# LEDmainb.net
KiCad netlist of a schematic drawn in Altium Designer
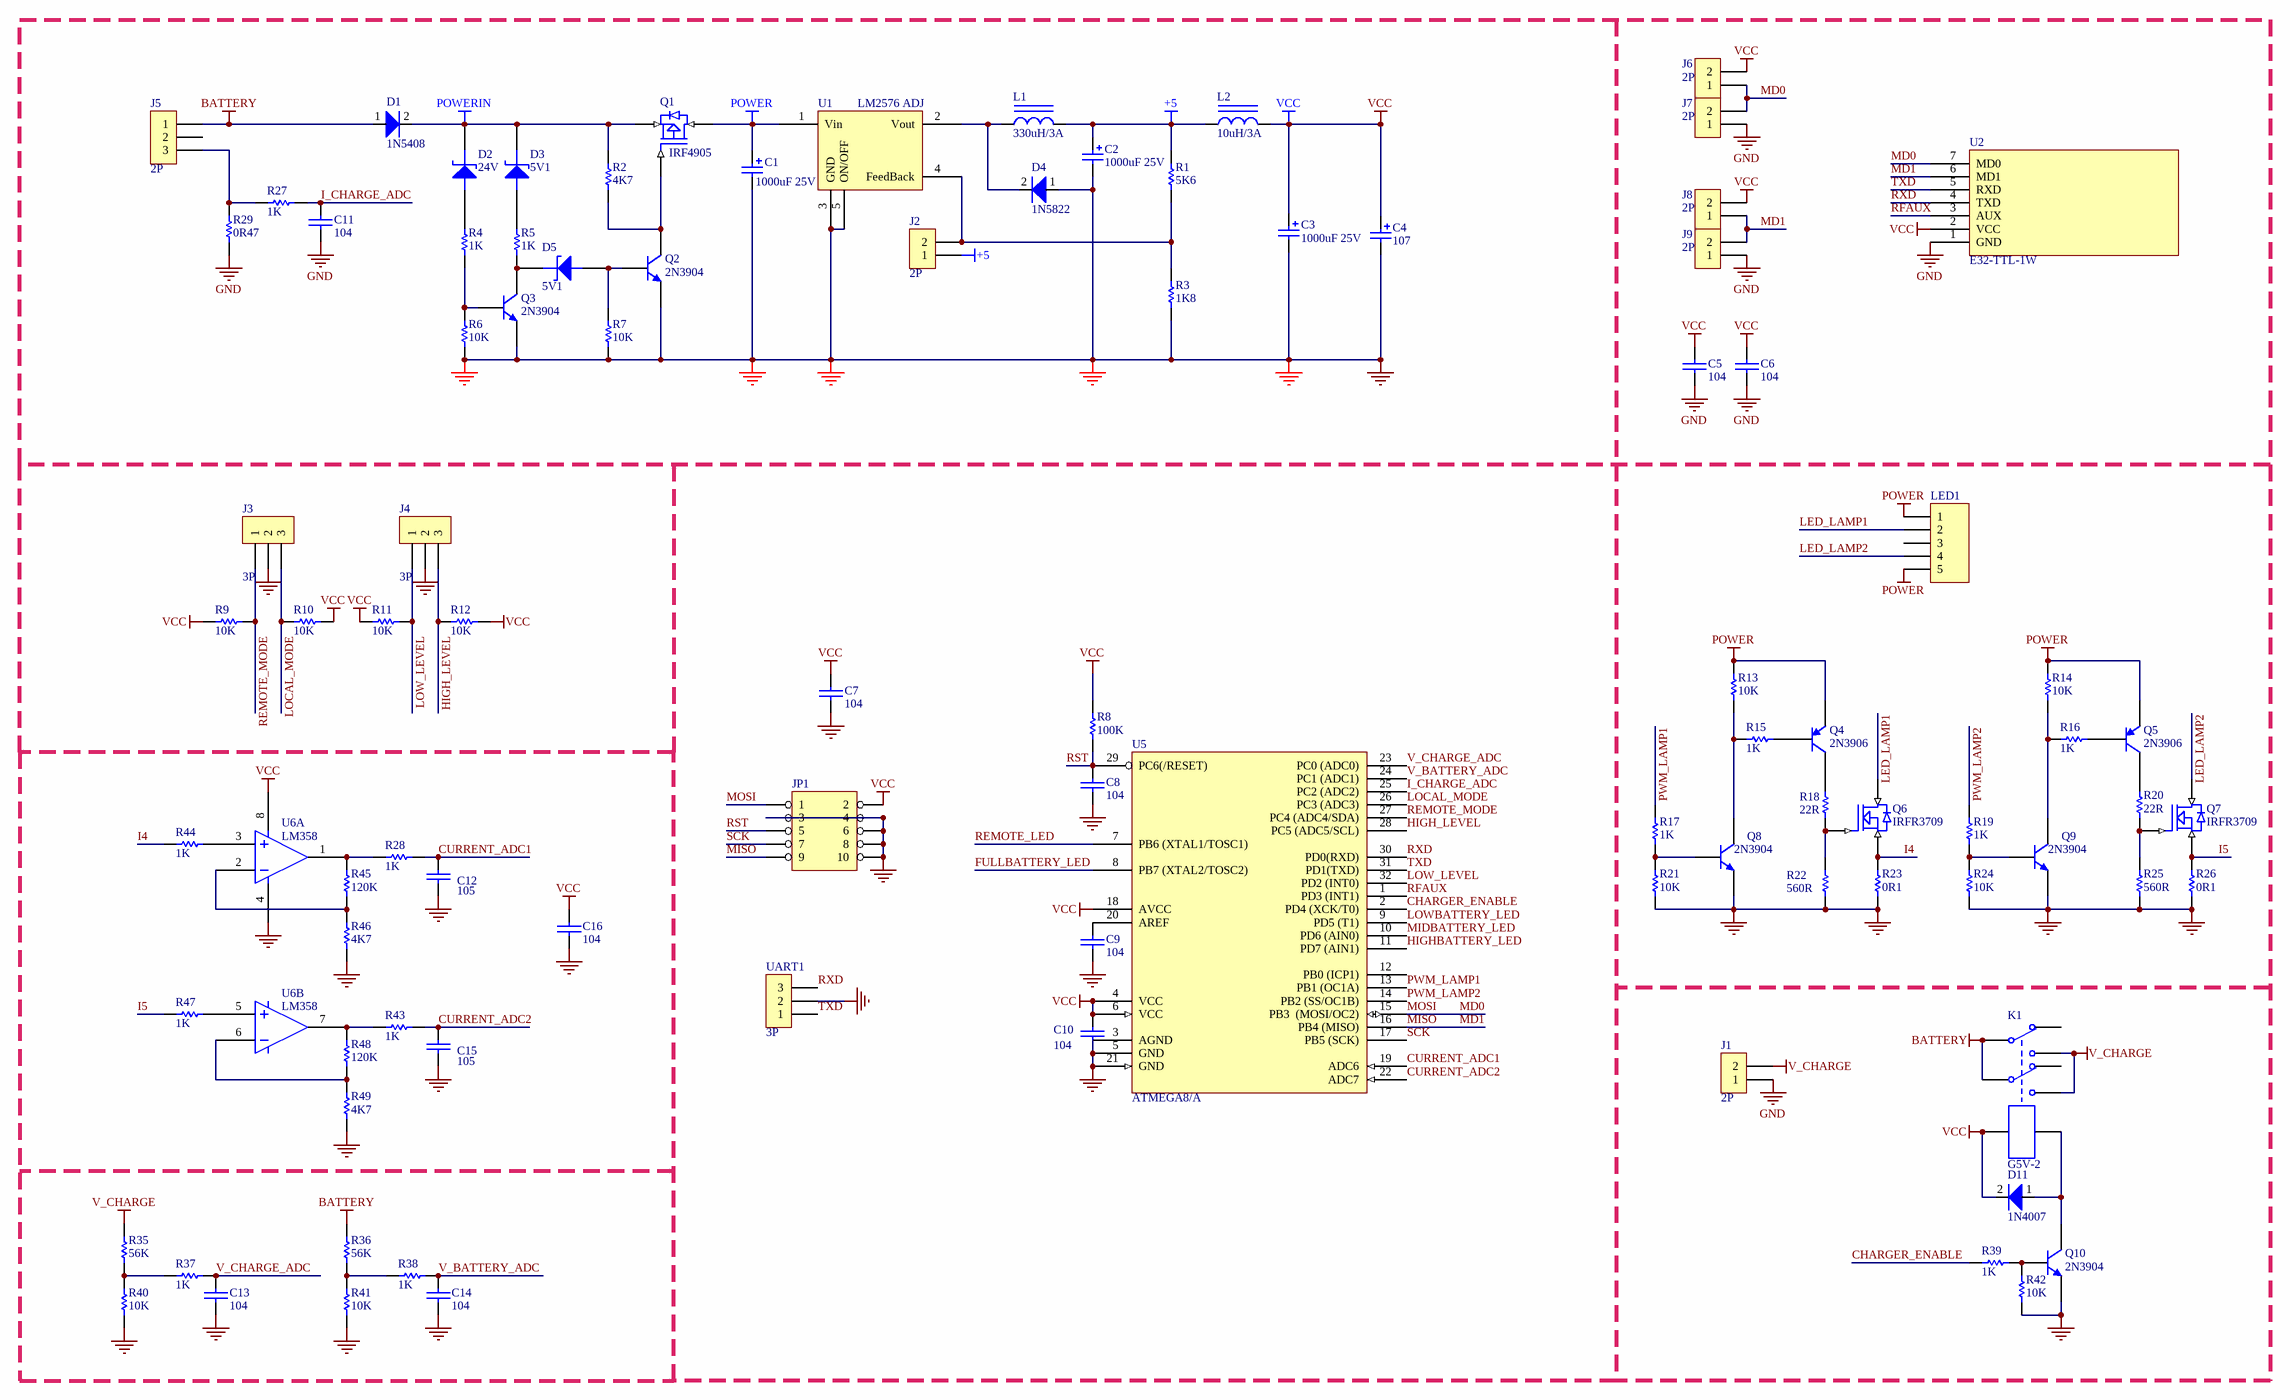
[diagram p0: LEDmainb.SchDoc]

(export (version "E")
  (design (tool "Eeschema 10.0.6"))
  (components
    (comp (ref "C1")
      (value "1000uF 25V")
      (footprint "CAP40x20L")
      (description "Polarized Capacitor (Radial)")
      (fields (field (name "Comment") "Tụ hóa chân cắm1000uF 25V") (field (name "PUBLISHER") "*"))
      (libsource (lib "DnsSchLib") (part "Cap Pol1"))
    )
    (comp (ref "C2")
      (value "1000uF 25V")
      (footprint "CAP40x20L")
      (description "Polarized Capacitor (Radial)")
      (fields (field (name "Comment") "Tụ hóa chân cắm1000uF 25V") (field (name "PUBLISHER") "*"))
      (libsource (lib "DnsSchLib") (part "Cap Pol1"))
    )
    (comp (ref "C3")
      (value "1000uF 25V")
      (footprint "CAP40x20L")
      (description "Polarized Capacitor (Radial)")
      (fields (field (name "Comment") "Tụ hóa chân cắm1000uF 25V") (field (name "PUBLISHER") "*"))
      (libsource (lib "DnsSchLib") (part "Cap Pol1"))
    )
    (comp (ref "C4")
      (value "107")
      (footprint "SMC_E/WA")
      (description "Polarized Capacitor (Radial)")
      (fields (field (name "Comment") "Tụ hóa chân dán107") (field (name "PUBLISHER") "*"))
      (libsource (lib "DnsSchLib") (part "Cap Pol1"))
    )
    (comp (ref "C5")
      (value "104")
      (footprint "0805C")
      (fields (field (name "Comment") "Tụ điện dán 0805104"))
      (libsource (lib "DnsSchLib") (part "CAP"))
    )
    (comp (ref "C6")
      (value "104")
      (footprint "0805C")
      (fields (field (name "Comment") "Tụ điện dán 0805104"))
      (libsource (lib "DnsSchLib") (part "CAP"))
    )
    (comp (ref "C7")
      (value "104")
      (footprint "0805C")
      (fields (field (name "Comment") "Tụ điện dán 0805104"))
      (libsource (lib "DnsSchLib") (part "CAP"))
    )
    (comp (ref "C8")
      (value "104")
      (footprint "0805C")
      (fields (field (name "Comment") "Tụ điện dán 0805104"))
      (libsource (lib "DnsSchLib") (part "CAP"))
    )
    (comp (ref "C9")
      (value "104")
      (footprint "0805C")
      (fields (field (name "Comment") "Tụ điện dán 0805104"))
      (libsource (lib "DnsSchLib") (part "CAP"))
    )
    (comp (ref "C10")
      (value "104")
      (footprint "0805C")
      (fields (field (name "Comment") "Tụ điện dán 0805104"))
      (libsource (lib "DnsSchLib") (part "CAP"))
    )
    (comp (ref "C11")
      (value "104")
      (footprint "0805C")
      (fields (field (name "Comment") "Tụ điện dán 0805104"))
      (libsource (lib "DnsSchLib") (part "CAP"))
    )
    (comp (ref "C12")
      (value "105")
      (footprint "0805C")
      (fields (field (name "Comment") "Tụ điện dán 0805105"))
      (libsource (lib "DnsSchLib") (part "CAP"))
    )
    (comp (ref "C13")
      (value "104")
      (footprint "0805C")
      (fields (field (name "Comment") "Tụ điện dán 0805104"))
      (libsource (lib "DnsSchLib") (part "CAP"))
    )
    (comp (ref "C14")
      (value "104")
      (footprint "0805C")
      (fields (field (name "Comment") "Tụ điện dán 0805104"))
      (libsource (lib "DnsSchLib") (part "CAP"))
    )
    (comp (ref "C15")
      (value "105")
      (footprint "0805C")
      (fields (field (name "Comment") "Tụ điện dán 0805105"))
      (libsource (lib "DnsSchLib") (part "CAP"))
    )
    (comp (ref "C16")
      (value "104")
      (footprint "0805C")
      (fields (field (name "Comment") "Tụ điện dán 0805104"))
      (libsource (lib "DnsSchLib") (part "CAP"))
    )
    (comp (ref "D1")
      (value "1N5408")
      (footprint "1N5408")
      (fields (field (name "Comment") "Diode chỉnh lưu chân cắm 3A1N5408"))
      (libsource (lib "DnsSchLib") (part "DIODE"))
    )
    (comp (ref "D2")
      (value "24V")
      (footprint "1N4148_S")
      (description "Zener Diode")
      (fields (field (name "Comment") "Diode ổn áp zener chân cắm 1W24V"))
      (libsource (lib "DnsSchLib") (part "ZENER2"))
    )
    (comp (ref "D3")
      (value "5V1")
      (footprint "1N4148_S")
      (description "Zener Diode")
      (fields (field (name "Comment") "Diode ổn áp zener chân cắm 1W5V1"))
      (libsource (lib "DnsSchLib") (part "ZENER2"))
    )
    (comp (ref "D4")
      (value "1N5822")
      (footprint "1N5822")
      (fields (field (name "Comment") "Diode xung chân cắm 3A1N5822"))
      (libsource (lib "DnsSchLib") (part "DIODE"))
    )
    (comp (ref "D5")
      (value "5V1")
      (footprint "1N4148_S")
      (description "Zener Diode")
      (fields (field (name "Comment") "Diode ổn áp zener chân cắm 1W5V1"))
      (libsource (lib "DnsSchLib") (part "ZENER2"))
    )
    (comp (ref "D11")
      (value "1N4007")
      (footprint "DIODE1A")
      (fields (field (name "Comment") "Diode chỉnh lưu chân cắm 1A1N4007"))
      (libsource (lib "DnsSchLib") (part "DIODE"))
    )
    (comp (ref "J1")
      (value "2P")
      (footprint "JACK381_2")
      (fields (field (name "Comment") "Giắc xanh loại nằm, 300V/16A - 3.81mm2P"))
      (libsource (lib "DnsSchLib") (part "CON2"))
    )
    (comp (ref "J2")
      (value "2P")
      (footprint "XPAD")
      (fields (field (name "Comment") "Jumper2P"))
      (libsource (lib "DnsSchLib") (part "CON2"))
    )
    (comp (ref "J3")
      (value "3P")
      (footprint "HDR1x3")
      (fields (field (name "Comment") "Jump đực chân thẳng, 2.54mm3P"))
      (libsource (lib "DnsSchLib") (part "CON3"))
    )
    (comp (ref "J4")
      (value "3P")
      (footprint "HDR1x3")
      (fields (field (name "Comment") "Jump đực chân thẳng, 2.54mm3P"))
      (libsource (lib "DnsSchLib") (part "CON3"))
    )
    (comp (ref "J5")
      (value "2P")
      (footprint "JACK381_3")
      (fields (field (name "Comment") "Giắc xanh loại nằm, 300V/16A - 3.81mm2P"))
      (libsource (lib "") (part "CON3_2"))
    )
    (comp (ref "J6")
      (value "2P")
      (footprint "XPAD")
      (fields (field (name "Comment") "Jumper2P"))
      (libsource (lib "DnsSchLib") (part "CON2"))
    )
    (comp (ref "J7")
      (value "2P")
      (footprint "XPAD")
      (fields (field (name "Comment") "Jumper2P"))
      (libsource (lib "DnsSchLib") (part "CON2"))
    )
    (comp (ref "J8")
      (value "2P")
      (footprint "XPAD")
      (fields (field (name "Comment") "Jumper2P"))
      (libsource (lib "DnsSchLib") (part "CON2"))
    )
    (comp (ref "J9")
      (value "2P")
      (footprint "XPAD")
      (fields (field (name "Comment") "Jumper2P"))
      (libsource (lib "DnsSchLib") (part "CON2"))
    )
    (comp (ref "JP1")
      (value "Jump đực chân thẳng, 2 hàng chân 2.54mm 10P")
      (footprint "HDR2X5")
      (libsource (lib "*") (part "HEADER 5X2"))
    )
    (comp (ref "K1")
      (value "G5V-2")
      (footprint "RELAY")
      (description "Dual-Pole Dual-Throw Relay")
      (fields (field (name "Comment") "Relay OMRON, 8 chân cắmG5V-2") (field (name "PUBLISHER") "*"))
      (libsource (lib "DnsSchLib") (part "Relay-DPDT"))
    )
    (comp (ref "L1")
      (value "330uH/3A")
      (footprint "CAMTRONDUNG")
      (fields (field (name "Comment") "Cuộn cảm chân cắm lõi trụ330uH/3A"))
      (libsource (lib "DnsSchLib") (part "INDUCTORSMALL"))
    )
    (comp (ref "L2")
      (value "10uH/3A")
      (footprint "CAMTRONDUNG")
      (fields (field (name "Comment") "Cuộn cảm chân cắm lõi trụ10uH/3A"))
      (libsource (lib "DnsSchLib") (part "INDUCTORSMALL"))
    )
    (comp (ref "LED1")
      (value "JUMP đực chân thẳng, 2.54mm 5P")
      (footprint "HDR1X5")
      (description "Header, 5-Pin")
      (fields (field (name "PUBLISHER") "Altium Limited"))
      (libsource (lib "Miscellaneous Connectors") (part "Header 5"))
    )
    (comp (ref "Q1")
      (value "IRF4905")
      (footprint "TO220SMD")
      (fields (field (name "Comment") "Transistor trường MOSFET P, chân dán TO-263IRF4905"))
      (libsource (lib "DnsSchLib") (part "MOSFET P"))
    )
    (comp (ref "Q2")
      (value "2N3904")
      (footprint "SOT23S")
      (description "NPN Bipolar Transistor")
      (fields
        (field (name "Comment") "Transistor BJT NPN, chân dán SOT-232N3904")
        (field (name "PUBLISHER") "*")
      )
      (libsource (lib "DnsSchLib") (part "NPN"))
    )
    (comp (ref "Q3")
      (value "2N3904")
      (footprint "SOT23S")
      (description "NPN Bipolar Transistor")
      (fields
        (field (name "Comment") "Transistor BJT NPN, chân dán SOT-232N3904")
        (field (name "PUBLISHER") "*")
      )
      (libsource (lib "DnsSchLib") (part "NPN"))
    )
    (comp (ref "Q4")
      (value "2N3906")
      (footprint "SOT23S")
      (description "PNP Bipolar Transistor")
      (fields
        (field (name "Comment") "Transistor BJT PNP, chân dán SOT-232N3906")
        (field (name "PUBLISHER") "*")
      )
      (libsource (lib "DnsSchLib") (part "PNP"))
    )
    (comp (ref "Q5")
      (value "2N3906")
      (footprint "SOT23S")
      (description "PNP Bipolar Transistor")
      (fields
        (field (name "Comment") "Transistor BJT PNP, chân dán SOT-232N3906")
        (field (name "PUBLISHER") "*")
      )
      (libsource (lib "DnsSchLib") (part "PNP"))
    )
    (comp (ref "Q6")
      (value "IRFR3709")
      (footprint "TO220HSMD")
      (fields (field (name "Comment") "Transistor trường MOSFET N, chân dán TO-263IRFR3709"))
      (libsource (lib "DnsSchLib") (part "MOSFET N"))
    )
    (comp (ref "Q7")
      (value "IRFR3709")
      (footprint "TO220HSMD")
      (fields (field (name "Comment") "Transistor trường MOSFET N, chân dán TO-263IRFR3709"))
      (libsource (lib "DnsSchLib") (part "MOSFET N"))
    )
    (comp (ref "Q8")
      (value "2N3904")
      (footprint "SOT23S")
      (description "NPN Bipolar Transistor")
      (fields
        (field (name "Comment") "Transistor BJT NPN, chân dán SOT-232N3904")
        (field (name "PUBLISHER") "*")
      )
      (libsource (lib "DnsSchLib") (part "NPN"))
    )
    (comp (ref "Q9")
      (value "2N3904")
      (footprint "SOT23S")
      (description "NPN Bipolar Transistor")
      (fields
        (field (name "Comment") "Transistor BJT NPN, chân dán SOT-232N3904")
        (field (name "PUBLISHER") "*")
      )
      (libsource (lib "DnsSchLib") (part "NPN"))
    )
    (comp (ref "Q10")
      (value "2N3904")
      (footprint "SOT23S")
      (description "NPN Bipolar Transistor")
      (fields
        (field (name "Comment") "Transistor BJT NPN, chân dán SOT-232N3904")
        (field (name "PUBLISHER") "*")
      )
      (libsource (lib "DnsSchLib") (part "NPN"))
    )
    (comp (ref "R1")
      (value "5K6")
      (footprint "0805DD")
      (description "Semiconductor Resistor")
      (fields (field (name "Comment") "Điện trở dán 08055K6") (field (name "PUBLISHER") "*"))
      (libsource (lib "DnsSchLib") (part "Res Semi"))
    )
    (comp (ref "R2")
      (value "4K7")
      (footprint "0805DD")
      (description "Semiconductor Resistor")
      (fields (field (name "Comment") "Điện trở dán 08054K7") (field (name "PUBLISHER") "*"))
      (libsource (lib "DnsSchLib") (part "Res Semi"))
    )
    (comp (ref "R3")
      (value "1K8")
      (footprint "0805DD")
      (description "Semiconductor Resistor")
      (fields (field (name "Comment") "Điện trở dán 08051K8") (field (name "PUBLISHER") "*"))
      (libsource (lib "DnsSchLib") (part "Res Semi"))
    )
    (comp (ref "R4")
      (value "1K")
      (footprint "0805DD")
      (description "Semiconductor Resistor")
      (fields (field (name "Comment") "Điện trở dán 08051K") (field (name "PUBLISHER") "*"))
      (libsource (lib "DnsSchLib") (part "Res Semi"))
    )
    (comp (ref "R5")
      (value "1K")
      (footprint "0805DD")
      (description "Semiconductor Resistor")
      (fields (field (name "Comment") "Điện trở dán 08051K") (field (name "PUBLISHER") "*"))
      (libsource (lib "DnsSchLib") (part "Res Semi"))
    )
    (comp (ref "R6")
      (value "10K")
      (footprint "0805DD")
      (description "Semiconductor Resistor")
      (fields (field (name "Comment") "Điện trở dán 080510K") (field (name "PUBLISHER") "*"))
      (libsource (lib "DnsSchLib") (part "Res Semi"))
    )
    (comp (ref "R7")
      (value "10K")
      (footprint "0805DD")
      (description "Semiconductor Resistor")
      (fields (field (name "Comment") "Điện trở dán 080510K") (field (name "PUBLISHER") "*"))
      (libsource (lib "DnsSchLib") (part "Res Semi"))
    )
    (comp (ref "R8")
      (value "100K")
      (footprint "0805DD")
      (description "Semiconductor Resistor")
      (fields (field (name "Comment") "Điện trở dán 0805100K") (field (name "PUBLISHER") "*"))
      (libsource (lib "DnsSchLib") (part "Res Semi"))
    )
    (comp (ref "R9")
      (value "10K")
      (footprint "0805DD")
      (description "Semiconductor Resistor")
      (fields (field (name "Comment") "Điện trở dán 080510K") (field (name "PUBLISHER") "*"))
      (libsource (lib "DnsSchLib") (part "Res Semi"))
    )
    (comp (ref "R10")
      (value "10K")
      (footprint "0805DD")
      (description "Semiconductor Resistor")
      (fields (field (name "Comment") "Điện trở dán 080510K") (field (name "PUBLISHER") "*"))
      (libsource (lib "DnsSchLib") (part "Res Semi"))
    )
    (comp (ref "R11")
      (value "10K")
      (footprint "0805DD")
      (description "Semiconductor Resistor")
      (fields (field (name "Comment") "Điện trở dán 080510K") (field (name "PUBLISHER") "*"))
      (libsource (lib "DnsSchLib") (part "Res Semi"))
    )
    (comp (ref "R12")
      (value "10K")
      (footprint "0805DD")
      (description "Semiconductor Resistor")
      (fields (field (name "Comment") "Điện trở dán 080510K") (field (name "PUBLISHER") "*"))
      (libsource (lib "DnsSchLib") (part "Res Semi"))
    )
    (comp (ref "R13")
      (value "10K")
      (footprint "0805DD")
      (description "Semiconductor Resistor")
      (fields (field (name "Comment") "Điện trở dán 080510K") (field (name "PUBLISHER") "*"))
      (libsource (lib "DnsSchLib") (part "Res Semi"))
    )
    (comp (ref "R14")
      (value "10K")
      (footprint "0805DD")
      (description "Semiconductor Resistor")
      (fields (field (name "Comment") "Điện trở dán 080510K") (field (name "PUBLISHER") "*"))
      (libsource (lib "DnsSchLib") (part "Res Semi"))
    )
    (comp (ref "R15")
      (value "1K")
      (footprint "0805DD")
      (description "Semiconductor Resistor")
      (fields (field (name "Comment") "Điện trở dán 08051K") (field (name "PUBLISHER") "*"))
      (libsource (lib "DnsSchLib") (part "Res Semi"))
    )
    (comp (ref "R16")
      (value "1K")
      (footprint "0805DD")
      (description "Semiconductor Resistor")
      (fields (field (name "Comment") "Điện trở dán 08051K") (field (name "PUBLISHER") "*"))
      (libsource (lib "DnsSchLib") (part "Res Semi"))
    )
    (comp (ref "R17")
      (value "1K")
      (footprint "0805DD")
      (description "Semiconductor Resistor")
      (fields (field (name "Comment") "Điện trở dán 08051K") (field (name "PUBLISHER") "*"))
      (libsource (lib "DnsSchLib") (part "Res Semi"))
    )
    (comp (ref "R18")
      (value "22R")
      (footprint "0805DD")
      (description "Semiconductor Resistor")
      (fields (field (name "Comment") "Điện trở dán 080522R") (field (name "PUBLISHER") "*"))
      (libsource (lib "DnsSchLib") (part "Res Semi"))
    )
    (comp (ref "R19")
      (value "1K")
      (footprint "0805DD")
      (description "Semiconductor Resistor")
      (fields (field (name "Comment") "Điện trở dán 08051K") (field (name "PUBLISHER") "*"))
      (libsource (lib "DnsSchLib") (part "Res Semi"))
    )
    (comp (ref "R20")
      (value "22R")
      (footprint "0805DD")
      (description "Semiconductor Resistor")
      (fields (field (name "Comment") "Điện trở dán 080522R") (field (name "PUBLISHER") "*"))
      (libsource (lib "DnsSchLib") (part "Res Semi"))
    )
    (comp (ref "R21")
      (value "10K")
      (footprint "0805DD")
      (description "Semiconductor Resistor")
      (fields (field (name "Comment") "Điện trở dán 080510K") (field (name "PUBLISHER") "*"))
      (libsource (lib "DnsSchLib") (part "Res Semi"))
    )
    (comp (ref "R22")
      (value "560R")
      (footprint "0805DD")
      (description "Semiconductor Resistor")
      (fields (field (name "Comment") "Điện trở dán 0805560R") (field (name "PUBLISHER") "*"))
      (libsource (lib "DnsSchLib") (part "Res Semi"))
    )
    (comp (ref "R23")
      (value "0R1")
      (footprint "AXIAL0.8S")
      (description "Semiconductor Resistor")
      (fields (field (name "Comment") "Điện trở chân cắm 2W0R1") (field (name "PUBLISHER") "*"))
      (libsource (lib "DnsSchLib") (part "Res Semi"))
    )
    (comp (ref "R24")
      (value "10K")
      (footprint "0805DD")
      (description "Semiconductor Resistor")
      (fields (field (name "Comment") "Điện trở dán 080510K") (field (name "PUBLISHER") "*"))
      (libsource (lib "DnsSchLib") (part "Res Semi"))
    )
    (comp (ref "R25")
      (value "560R")
      (footprint "0805DD")
      (description "Semiconductor Resistor")
      (fields (field (name "Comment") "Điện trở dán 0805560R") (field (name "PUBLISHER") "*"))
      (libsource (lib "DnsSchLib") (part "Res Semi"))
    )
    (comp (ref "R26")
      (value "0R1")
      (footprint "AXIAL0.8S")
      (description "Semiconductor Resistor")
      (fields (field (name "Comment") "Điện trở chân cắm 2W0R1") (field (name "PUBLISHER") "*"))
      (libsource (lib "DnsSchLib") (part "Res Semi"))
    )
    (comp (ref "R27")
      (value "1K")
      (footprint "0805DD")
      (description "Semiconductor Resistor")
      (fields (field (name "Comment") "Điện trở dán 08051K") (field (name "PUBLISHER") "*"))
      (libsource (lib "DnsSchLib") (part "Res Semi"))
    )
    (comp (ref "R28")
      (value "1K")
      (footprint "0805DD")
      (description "Semiconductor Resistor")
      (fields (field (name "Comment") "Điện trở dán 08051K") (field (name "PUBLISHER") "*"))
      (libsource (lib "DnsSchLib") (part "Res Semi"))
    )
    (comp (ref "R29")
      (value "0R47")
      (footprint "AXIAL0.8S")
      (description "Semiconductor Resistor")
      (fields (field (name "Comment") "Điện trở chân cắm 2W0R47") (field (name "PUBLISHER") "*"))
      (libsource (lib "DnsSchLib") (part "Res Semi"))
    )
    (comp (ref "R35")
      (value "56K")
      (footprint "0805DD")
      (description "Semiconductor Resistor")
      (fields (field (name "Comment") "Điện trở dán 0805 1%56K") (field (name "PUBLISHER") "*"))
      (libsource (lib "DnsSchLib") (part "Res Semi"))
    )
    (comp (ref "R36")
      (value "56K")
      (footprint "0805DD")
      (description "Semiconductor Resistor")
      (fields (field (name "Comment") "Điện trở dán 0805 1%56K") (field (name "PUBLISHER") "*"))
      (libsource (lib "DnsSchLib") (part "Res Semi"))
    )
    (comp (ref "R37")
      (value "1K")
      (footprint "0805DD")
      (description "Semiconductor Resistor")
      (fields (field (name "Comment") "Điện trở dán 08051K") (field (name "PUBLISHER") "*"))
      (libsource (lib "DnsSchLib") (part "Res Semi"))
    )
    (comp (ref "R38")
      (value "1K")
      (footprint "0805DD")
      (description "Semiconductor Resistor")
      (fields (field (name "Comment") "Điện trở dán 08051K") (field (name "PUBLISHER") "*"))
      (libsource (lib "DnsSchLib") (part "Res Semi"))
    )
    (comp (ref "R39")
      (value "1K")
      (footprint "0805DD")
      (description "Semiconductor Resistor")
      (fields (field (name "Comment") "Điện trở dán 08051K") (field (name "PUBLISHER") "*"))
      (libsource (lib "DnsSchLib") (part "Res Semi"))
    )
    (comp (ref "R40")
      (value "10K")
      (footprint "0805DD")
      (description "Semiconductor Resistor")
      (fields (field (name "Comment") "Điện trở dán 0805 1%10K") (field (name "PUBLISHER") "*"))
      (libsource (lib "DnsSchLib") (part "Res Semi"))
    )
    (comp (ref "R41")
      (value "10K")
      (footprint "0805DD")
      (description "Semiconductor Resistor")
      (fields (field (name "Comment") "Điện trở dán 0805 1%10K") (field (name "PUBLISHER") "*"))
      (libsource (lib "DnsSchLib") (part "Res Semi"))
    )
    (comp (ref "R42")
      (value "10K")
      (footprint "0805DD")
      (description "Semiconductor Resistor")
      (fields (field (name "Comment") "Điện trở dán 080510K") (field (name "PUBLISHER") "*"))
      (libsource (lib "DnsSchLib") (part "Res Semi"))
    )
    (comp (ref "R43")
      (value "1K")
      (footprint "0805DD")
      (description "Semiconductor Resistor")
      (fields (field (name "Comment") "Điện trở dán 08051K") (field (name "PUBLISHER") "*"))
      (libsource (lib "DnsSchLib") (part "Res Semi"))
    )
    (comp (ref "R44")
      (value "1K")
      (footprint "0805DD")
      (description "Semiconductor Resistor")
      (fields (field (name "Comment") "Điện trở dán 08051K") (field (name "PUBLISHER") "*"))
      (libsource (lib "DnsSchLib") (part "Res Semi"))
    )
    (comp (ref "R45")
      (value "120K")
      (footprint "0805DD")
      (description "Semiconductor Resistor")
      (fields (field (name "Comment") "Điện trở dán 0805 1%120K") (field (name "PUBLISHER") "*"))
      (libsource (lib "DnsSchLib") (part "Res Semi"))
    )
    (comp (ref "R46")
      (value "4K7")
      (footprint "0805DD")
      (description "Semiconductor Resistor")
      (fields (field (name "Comment") "Điện trở dán 0805 1%4K7") (field (name "PUBLISHER") "*"))
      (libsource (lib "DnsSchLib") (part "Res Semi"))
    )
    (comp (ref "R47")
      (value "1K")
      (footprint "0805DD")
      (description "Semiconductor Resistor")
      (fields (field (name "Comment") "Điện trở dán 08051K") (field (name "PUBLISHER") "*"))
      (libsource (lib "DnsSchLib") (part "Res Semi"))
    )
    (comp (ref "R48")
      (value "120K")
      (footprint "0805DD")
      (description "Semiconductor Resistor")
      (fields (field (name "Comment") "Điện trở dán 0805 1%120K") (field (name "PUBLISHER") "*"))
      (libsource (lib "DnsSchLib") (part "Res Semi"))
    )
    (comp (ref "R49")
      (value "4K7")
      (footprint "0805DD")
      (description "Semiconductor Resistor")
      (fields (field (name "Comment") "Điện trở dán 0805 1%4K7") (field (name "PUBLISHER") "*"))
      (libsource (lib "DnsSchLib") (part "Res Semi"))
    )
    (comp (ref "U1")
      (value "LM2576 ADJ")
      (footprint "TO220_5CSMD2")
      (fields (field (name "Comment") "IC chuyển đổi nguồn, chân dánLM2576 ADJ"))
      (libsource (lib "DnsSchLib") (part "LM2576"))
    )
    (comp (ref "U2")
      (value "E32-TTL-1W")
      (footprint "RF_AS32")
      (description "AS32-TTL-1W")
      (fields (field (name "Comment") "Module thu phát không dây RFE32-TTL-1W"))
      (libsource (lib "DnsSchLib") (part "AS32-TTL-1W"))
    )
    (comp (ref "U5")
      (value "ATMEGA8/A")
      (footprint "ATMEGA8")
      (description "TQFP package")
      (fields (field (name "Comment") "Vi điều khiển ATMEL chân dánATMEGA8/A"))
      (libsource (lib "DnsSchLib") (part "ATMEGA8-A"))
    )
    (comp (ref "U6")
      (value "IC khuếch đại thuật toán LM358 chân dán SO-8")
      (footprint "so-8")
      (fields (field (name "NAME") "LM358"))
      (libsource (lib "DnsSchLib") (part "1458"))
    )
    (comp (ref "UART1")
      (value "3P")
      (footprint "HDR1x3")
      (fields (field (name "Comment") "Jump đực chân thẳng, 2.54mm3P"))
      (libsource (lib "") (part "CON3_1"))
    )
  )
  (nets
    (net (code "1") (name "+5") (class "Default")
      (node (ref "C2") (pin "1") (pinfunction "1_1") (pintype "passive"))
      (node (ref "J2") (pin "1") (pinfunction "1_1") (pintype "passive"))
      (node (ref "L1") (pin "2") (pinfunction "2_2") (pintype "passive"))
      (node (ref "L2") (pin "1") (pinfunction "1_1") (pintype "passive"))
      (node (ref "R1") (pin "2") (pinfunction "2_2") (pintype "passive"))
    )
    (net (code "2") (name "/CHARGER_ENABLE") (class "Default")
      (node (ref "R39") (pin "2") (pinfunction "2_2") (pintype "passive"))
      (node (ref "U5") (pin "2") (pinfunction "PD4_(XCK/T0)_2") (pintype "passive"))
    )
    (net (code "3") (name "/CURRENT_ADC1") (class "Default")
      (node (ref "C12") (pin "1") (pinfunction "1_1") (pintype "passive"))
      (node (ref "R28") (pin "1") (pinfunction "1_1") (pintype "passive"))
      (node (ref "U5") (pin "19") (pinfunction "ADC6_19") (pintype "input"))
    )
    (net (code "4") (name "/CURRENT_ADC2") (class "Default")
      (node (ref "C15") (pin "1") (pinfunction "1_1") (pintype "passive"))
      (node (ref "R43") (pin "1") (pinfunction "1_1") (pintype "passive"))
      (node (ref "U5") (pin "22") (pinfunction "ADC7_22") (pintype "input"))
    )
    (net (code "5") (name "/FULLBATTERY_LED") (class "Default")
      (node (ref "U5") (pin "8") (pinfunction "PB7_(XTAL2/TOSC2)_8") (pintype "passive"))
    )
    (net (code "6") (name "/HIGHBATTERY_LED") (class "Default")
      (node (ref "U5") (pin "11") (pinfunction "PD7_(AIN1)_11") (pintype "passive"))
    )
    (net (code "7") (name "/HIGH_LEVEL") (class "Default")
      (node (ref "J4") (pin "3") (pinfunction "3_3") (pintype "passive"))
      (node (ref "R12") (pin "2") (pinfunction "2_2") (pintype "passive"))
      (node (ref "U5") (pin "28") (pinfunction "PC5_(ADC5/SCL)_28") (pintype "passive"))
    )
    (net (code "8") (name "/I4") (class "Default")
      (node (ref "Q6") (pin "3") (pinfunction "S_3") (pintype "input"))
      (node (ref "R23") (pin "2") (pinfunction "2_2") (pintype "passive"))
      (node (ref "R44") (pin "1") (pinfunction "1_1") (pintype "passive"))
    )
    (net (code "9") (name "/I5") (class "Default")
      (node (ref "Q7") (pin "3") (pinfunction "S_3") (pintype "input"))
      (node (ref "R26") (pin "2") (pinfunction "2_2") (pintype "passive"))
      (node (ref "R47") (pin "1") (pinfunction "1_1") (pintype "passive"))
    )
    (net (code "10") (name "/I_CHARGE_ADC") (class "Default")
      (node (ref "C11") (pin "1") (pinfunction "1_1") (pintype "passive"))
      (node (ref "R27") (pin "2") (pinfunction "2_2") (pintype "passive"))
      (node (ref "U5") (pin "25") (pinfunction "PC2_(ADC2)_25") (pintype "passive"))
    )
    (net (code "11") (name "/LED_LAMP1") (class "Default")
      (node (ref "LED1") (pin "2") (pinfunction "2_2") (pintype "passive"))
      (node (ref "Q6") (pin "2") (pinfunction "D_2") (pintype "input"))
    )
    (net (code "12") (name "/LED_LAMP2") (class "Default")
      (node (ref "LED1") (pin "4") (pinfunction "4_4") (pintype "passive"))
      (node (ref "Q7") (pin "2") (pinfunction "D_2") (pintype "input"))
    )
    (net (code "13") (name "/LOCAL_MODE") (class "Default")
      (node (ref "J3") (pin "3") (pinfunction "3_3") (pintype "passive"))
      (node (ref "R10") (pin "1") (pinfunction "1_1") (pintype "passive"))
      (node (ref "U5") (pin "26") (pinfunction "PC3_(ADC3)_26") (pintype "passive"))
    )
    (net (code "14") (name "/LOWBATTERY_LED") (class "Default")
      (node (ref "U5") (pin "9") (pinfunction "PD5_(T1)_9") (pintype "passive"))
    )
    (net (code "15") (name "/LOW_LEVEL") (class "Default")
      (node (ref "J4") (pin "1") (pinfunction "1_1") (pintype "passive"))
      (node (ref "R11") (pin "2") (pinfunction "2_2") (pintype "passive"))
      (node (ref "U5") (pin "32") (pinfunction "PD2_(INT0)_32") (pintype "passive"))
    )
    (net (code "16") (name "/MD0") (class "Default")
      (node (ref "J6") (pin "1") (pinfunction "1_1") (pintype "passive"))
      (node (ref "J7") (pin "2") (pinfunction "2_2") (pintype "passive"))
      (node (ref "JP1") (pin "1") (pinfunction "1_1") (pintype "passive"))
      (node (ref "U2") (pin "7") (pinfunction "MD0_7") (pintype "passive"))
      (node (ref "U5") (pin "15") (pinfunction "PB3__(MOSI/OC2)_15") (pintype "bidirectional"))
    )
    (net (code "17") (name "/MD1") (class "Default")
      (node (ref "J8") (pin "1") (pinfunction "1_1") (pintype "passive"))
      (node (ref "J9") (pin "2") (pinfunction "2_2") (pintype "passive"))
      (node (ref "JP1") (pin "9") (pinfunction "9_9") (pintype "passive"))
      (node (ref "U2") (pin "6") (pinfunction "MD1_6") (pintype "passive"))
      (node (ref "U5") (pin "16") (pinfunction "PB4_(MISO)_16") (pintype "passive"))
    )
    (net (code "18") (name "/MIDBATTERY_LED") (class "Default")
      (node (ref "U5") (pin "10") (pinfunction "PD6_(AIN0)_10") (pintype "passive"))
    )
    (net (code "19") (name "/PWM_LAMP1") (class "Default")
      (node (ref "R17") (pin "1") (pinfunction "1_1") (pintype "passive"))
      (node (ref "U5") (pin "13") (pinfunction "PB1_(OC1A)_13") (pintype "passive"))
    )
    (net (code "20") (name "/PWM_LAMP2") (class "Default")
      (node (ref "R19") (pin "1") (pinfunction "1_1") (pintype "passive"))
      (node (ref "U5") (pin "14") (pinfunction "PB2_(SS/OC1B)_14") (pintype "passive"))
    )
    (net (code "21") (name "/REMOTE_LED") (class "Default")
      (node (ref "U5") (pin "7") (pinfunction "PB6_(XTAL1/TOSC1)_7") (pintype "passive"))
    )
    (net (code "22") (name "/REMOTE_MODE") (class "Default")
      (node (ref "J3") (pin "1") (pinfunction "1_1") (pintype "passive"))
      (node (ref "R9") (pin "1") (pinfunction "1_1") (pintype "passive"))
      (node (ref "U5") (pin "27") (pinfunction "PC4_(ADC4/SDA)_27") (pintype "passive"))
    )
    (net (code "23") (name "/RFAUX") (class "Default")
      (node (ref "U2") (pin "3") (pinfunction "AUX_3") (pintype "passive"))
      (node (ref "U5") (pin "1") (pinfunction "PD3_(INT1)_1") (pintype "passive"))
    )
    (net (code "24") (name "/RST") (class "Default")
      (node (ref "C8") (pin "1") (pinfunction "1_1") (pintype "passive"))
      (node (ref "JP1") (pin "5") (pinfunction "5_5") (pintype "passive"))
      (node (ref "R8") (pin "1") (pinfunction "1_1") (pintype "passive"))
      (node (ref "U5") (pin "29") (pinfunction "PC6(/RESET)_29") (pintype "passive"))
    )
    (net (code "25") (name "/RXD") (class "Default")
      (node (ref "U2") (pin "4") (pinfunction "TXD_4") (pintype "passive"))
      (node (ref "U5") (pin "30") (pinfunction "PD0(RXD)_30") (pintype "passive"))
      (node (ref "UART1") (pin "3") (pinfunction "3_3") (pintype "passive"))
    )
    (net (code "26") (name "/SCK") (class "Default")
      (node (ref "JP1") (pin "7") (pinfunction "7_7") (pintype "passive"))
      (node (ref "U5") (pin "17") (pinfunction "PB5_(SCK)_17") (pintype "passive"))
    )
    (net (code "27") (name "/TXD") (class "Default")
      (node (ref "U2") (pin "5") (pinfunction "RXD_5") (pintype "passive"))
      (node (ref "U5") (pin "31") (pinfunction "PD1(TXD)_31") (pintype "passive"))
      (node (ref "UART1") (pin "1") (pinfunction "1_1") (pintype "passive"))
    )
    (net (code "28") (name "/V_BATTERY_ADC") (class "Default")
      (node (ref "C14") (pin "1") (pinfunction "1_1") (pintype "passive"))
      (node (ref "R38") (pin "2") (pinfunction "2_2") (pintype "passive"))
      (node (ref "U5") (pin "24") (pinfunction "PC1_(ADC1)_24") (pintype "passive"))
    )
    (net (code "29") (name "/V_CHARGE_ADC") (class "Default")
      (node (ref "C13") (pin "1") (pinfunction "1_1") (pintype "passive"))
      (node (ref "R37") (pin "2") (pinfunction "2_2") (pintype "passive"))
      (node (ref "U5") (pin "23") (pinfunction "PC0_(ADC0)_23") (pintype "passive"))
    )
    (net (code "30") (name "BATTERY") (class "Default")
      (node (ref "D1") (pin "1") (pinfunction "A_1") (pintype "passive"))
      (node (ref "J5") (pin "1") (pinfunction "1_1") (pintype "passive"))
      (node (ref "K1") (pin "1") (pinfunction "1_1") (pintype "passive"))
      (node (ref "K1") (pin "4") (pinfunction "4_4") (pintype "passive"))
      (node (ref "R36") (pin "2") (pinfunction "2_2") (pintype "passive"))
    )
    (net (code "31") (name "GND") (class "Default")
      (node (ref "C1") (pin "2") (pinfunction "2_2") (pintype "passive"))
      (node (ref "C10") (pin "1") (pinfunction "1_1") (pintype "passive"))
      (node (ref "C11") (pin "2") (pinfunction "2_2") (pintype "passive"))
      (node (ref "C12") (pin "2") (pinfunction "2_2") (pintype "passive"))
      (node (ref "C13") (pin "2") (pinfunction "2_2") (pintype "passive"))
      (node (ref "C14") (pin "2") (pinfunction "2_2") (pintype "passive"))
      (node (ref "C15") (pin "2") (pinfunction "2_2") (pintype "passive"))
      (node (ref "C16") (pin "1") (pinfunction "1_1") (pintype "passive"))
      (node (ref "C2") (pin "2") (pinfunction "2_2") (pintype "passive"))
      (node (ref "C3") (pin "2") (pinfunction "2_2") (pintype "passive"))
      (node (ref "C4") (pin "2") (pinfunction "2_2") (pintype "passive"))
      (node (ref "C5") (pin "2") (pinfunction "2_2") (pintype "passive"))
      (node (ref "C6") (pin "1") (pinfunction "1_1") (pintype "passive"))
      (node (ref "C7") (pin "1") (pinfunction "1_1") (pintype "passive"))
      (node (ref "C8") (pin "2") (pinfunction "2_2") (pintype "passive"))
      (node (ref "C9") (pin "1") (pinfunction "1_1") (pintype "passive"))
      (node (ref "D4") (pin "1") (pinfunction "A_1") (pintype "passive"))
      (node (ref "J1") (pin "1") (pinfunction "1_1") (pintype "passive"))
      (node (ref "J3") (pin "2") (pinfunction "2_2") (pintype "passive"))
      (node (ref "J4") (pin "2") (pinfunction "2_2") (pintype "passive"))
      (node (ref "J7") (pin "1") (pinfunction "1_1") (pintype "passive"))
      (node (ref "J9") (pin "1") (pinfunction "1_1") (pintype "passive"))
      (node (ref "JP1") (pin "10") (pinfunction "10_10") (pintype "passive"))
      (node (ref "JP1") (pin "3") (pinfunction "3_3") (pintype "passive"))
      (node (ref "JP1") (pin "4") (pinfunction "4_4") (pintype "passive"))
      (node (ref "JP1") (pin "6") (pinfunction "6_6") (pintype "passive"))
      (node (ref "JP1") (pin "8") (pinfunction "8_8") (pintype "passive"))
      (node (ref "Q10") (pin "3") (pinfunction "E_3") (pintype "passive"))
      (node (ref "Q2") (pin "3") (pinfunction "E_3") (pintype "passive"))
      (node (ref "Q3") (pin "3") (pinfunction "E_3") (pintype "passive"))
      (node (ref "Q8") (pin "3") (pinfunction "E_3") (pintype "passive"))
      (node (ref "Q9") (pin "3") (pinfunction "E_3") (pintype "passive"))
      (node (ref "R21") (pin "1") (pinfunction "1_1") (pintype "passive"))
      (node (ref "R22") (pin "2") (pinfunction "2_2") (pintype "passive"))
      (node (ref "R23") (pin "1") (pinfunction "1_1") (pintype "passive"))
      (node (ref "R24") (pin "1") (pinfunction "1_1") (pintype "passive"))
      (node (ref "R25") (pin "2") (pinfunction "2_2") (pintype "passive"))
      (node (ref "R26") (pin "1") (pinfunction "1_1") (pintype "passive"))
      (node (ref "R29") (pin "1") (pinfunction "1_1") (pintype "passive"))
      (node (ref "R3") (pin "1") (pinfunction "1_1") (pintype "passive"))
      (node (ref "R40") (pin "1") (pinfunction "1_1") (pintype "passive"))
      (node (ref "R41") (pin "1") (pinfunction "1_1") (pintype "passive"))
      (node (ref "R42") (pin "1") (pinfunction "1_1") (pintype "passive"))
      (node (ref "R46") (pin "1") (pinfunction "1_1") (pintype "passive"))
      (node (ref "R49") (pin "2") (pinfunction "2_2") (pintype "passive"))
      (node (ref "R6") (pin "1") (pinfunction "1_1") (pintype "passive"))
      (node (ref "R7") (pin "1") (pinfunction "1_1") (pintype "passive"))
      (node (ref "U1") (pin "3") (pinfunction "GND_3") (pintype "passive"))
      (node (ref "U1") (pin "5") (pinfunction "ON/OFF_5") (pintype "passive"))
      (node (ref "U2") (pin "1") (pinfunction "GND_1") (pintype "passive"))
      (node (ref "U5") (pin "21") (pinfunction "GND_21") (pintype "input"))
      (node (ref "U5") (pin "3") (pinfunction "AGND_3") (pintype "passive"))
      (node (ref "U5") (pin "5") (pinfunction "GND_5") (pintype "passive"))
      (node (ref "U6") (pin "4") (pintype "passive"))
      (node (ref "UART1") (pin "2") (pinfunction "2_2") (pintype "passive"))
    )
    (net (code "32") (name "Net-(D2-A)") (class "Default")
      (node (ref "D2") (pin "1") (pinfunction "A_1") (pintype "passive"))
      (node (ref "R4") (pin "2") (pinfunction "2_2") (pintype "passive"))
    )
    (net (code "33") (name "Net-(D3-A)") (class "Default")
      (node (ref "D3") (pin "1") (pinfunction "A_1") (pintype "passive"))
      (node (ref "R5") (pin "2") (pinfunction "2_2") (pintype "passive"))
    )
    (net (code "34") (name "Net-(D4-K)") (class "Default")
      (node (ref "D4") (pin "2") (pinfunction "K_2") (pintype "passive"))
      (node (ref "L1") (pin "1") (pinfunction "1_1") (pintype "passive"))
      (node (ref "U1") (pin "2") (pinfunction "Vout_2") (pintype "passive"))
    )
    (net (code "35") (name "Net-(D5-A)") (class "Default")
      (node (ref "D5") (pin "1") (pinfunction "A_1") (pintype "passive"))
      (node (ref "Q2") (pin "1") (pinfunction "B_1") (pintype "passive"))
      (node (ref "R7") (pin "2") (pinfunction "2_2") (pintype "passive"))
    )
    (net (code "36") (name "Net-(D5-K)") (class "Default")
      (node (ref "D5") (pin "2") (pinfunction "K_2") (pintype "passive"))
      (node (ref "Q3") (pin "2") (pinfunction "C_2") (pintype "passive"))
      (node (ref "R5") (pin "1") (pinfunction "1_1") (pintype "passive"))
    )
    (net (code "37") (name "Net-(D11-A)") (class "Default")
      (node (ref "D11") (pin "1") (pinfunction "A_1") (pintype "passive"))
      (node (ref "K1") (pin "8") (pinfunction "8_8") (pintype "passive"))
      (node (ref "Q10") (pin "2") (pinfunction "C_2") (pintype "passive"))
    )
    (net (code "38") (name "Net-(J5-Pad3)") (class "Default")
      (node (ref "J5") (pin "3") (pinfunction "3_3") (pintype "passive"))
      (node (ref "R27") (pin "1") (pinfunction "1_1") (pintype "passive"))
      (node (ref "R29") (pin "2") (pinfunction "2_2") (pintype "passive"))
    )
    (net (code "39") (name "Net-(Q1-G)") (class "Default")
      (node (ref "Q1") (pin "1") (pinfunction "G_1") (pintype "input"))
      (node (ref "Q2") (pin "2") (pinfunction "C_2") (pintype "passive"))
      (node (ref "R2") (pin "1") (pinfunction "1_1") (pintype "passive"))
    )
    (net (code "40") (name "Net-(Q3-B)") (class "Default")
      (node (ref "Q3") (pin "1") (pinfunction "B_1") (pintype "passive"))
      (node (ref "R4") (pin "1") (pinfunction "1_1") (pintype "passive"))
      (node (ref "R6") (pin "2") (pinfunction "2_2") (pintype "passive"))
    )
    (net (code "41") (name "Net-(Q4-B)") (class "Default")
      (node (ref "Q4") (pin "1") (pinfunction "B_1") (pintype "passive"))
      (node (ref "R15") (pin "1") (pinfunction "1_1") (pintype "passive"))
    )
    (net (code "42") (name "Net-(Q4-C)") (class "Default")
      (node (ref "Q4") (pin "2") (pinfunction "C_2") (pintype "passive"))
      (node (ref "R18") (pin "1") (pinfunction "1_1") (pintype "passive"))
    )
    (net (code "43") (name "Net-(Q5-B)") (class "Default")
      (node (ref "Q5") (pin "1") (pinfunction "B_1") (pintype "passive"))
      (node (ref "R16") (pin "1") (pinfunction "1_1") (pintype "passive"))
    )
    (net (code "44") (name "Net-(Q5-C)") (class "Default")
      (node (ref "Q5") (pin "2") (pinfunction "C_2") (pintype "passive"))
      (node (ref "R20") (pin "1") (pinfunction "1_1") (pintype "passive"))
    )
    (net (code "45") (name "Net-(Q6-G)") (class "Default")
      (node (ref "Q6") (pin "1") (pinfunction "G_1") (pintype "input"))
      (node (ref "R18") (pin "2") (pinfunction "2_2") (pintype "passive"))
      (node (ref "R22") (pin "1") (pinfunction "1_1") (pintype "passive"))
    )
    (net (code "46") (name "Net-(Q7-G)") (class "Default")
      (node (ref "Q7") (pin "1") (pinfunction "G_1") (pintype "input"))
      (node (ref "R20") (pin "2") (pinfunction "2_2") (pintype "passive"))
      (node (ref "R25") (pin "1") (pinfunction "1_1") (pintype "passive"))
    )
    (net (code "47") (name "Net-(Q8-B)") (class "Default")
      (node (ref "Q8") (pin "1") (pinfunction "B_1") (pintype "passive"))
      (node (ref "R17") (pin "2") (pinfunction "2_2") (pintype "passive"))
      (node (ref "R21") (pin "2") (pinfunction "2_2") (pintype "passive"))
    )
    (net (code "48") (name "Net-(Q8-C)") (class "Default")
      (node (ref "Q8") (pin "2") (pinfunction "C_2") (pintype "passive"))
      (node (ref "R13") (pin "1") (pinfunction "1_1") (pintype "passive"))
      (node (ref "R15") (pin "2") (pinfunction "2_2") (pintype "passive"))
    )
    (net (code "49") (name "Net-(Q9-B)") (class "Default")
      (node (ref "Q9") (pin "1") (pinfunction "B_1") (pintype "passive"))
      (node (ref "R19") (pin "2") (pinfunction "2_2") (pintype "passive"))
      (node (ref "R24") (pin "2") (pinfunction "2_2") (pintype "passive"))
    )
    (net (code "50") (name "Net-(Q9-C)") (class "Default")
      (node (ref "Q9") (pin "2") (pinfunction "C_2") (pintype "passive"))
      (node (ref "R14") (pin "1") (pinfunction "1_1") (pintype "passive"))
      (node (ref "R16") (pin "2") (pinfunction "2_2") (pintype "passive"))
    )
    (net (code "51") (name "Net-(Q10-B)") (class "Default")
      (node (ref "Q10") (pin "1") (pinfunction "B_1") (pintype "passive"))
      (node (ref "R39") (pin "1") (pinfunction "1_1") (pintype "passive"))
      (node (ref "R42") (pin "2") (pinfunction "2_2") (pintype "passive"))
    )
    (net (code "52") (name "Net-(R28-Pad2)") (class "Default")
      (node (ref "R28") (pin "2") (pinfunction "2_2") (pintype "passive"))
      (node (ref "R45") (pin "2") (pinfunction "2_2") (pintype "passive"))
      (node (ref "U6") (pin "1") (pintype "passive"))
    )
    (net (code "53") (name "Net-(R35-Pad1)") (class "Default")
      (node (ref "R35") (pin "1") (pinfunction "1_1") (pintype "passive"))
      (node (ref "R37") (pin "1") (pinfunction "1_1") (pintype "passive"))
      (node (ref "R40") (pin "2") (pinfunction "2_2") (pintype "passive"))
    )
    (net (code "54") (name "Net-(R36-Pad1)") (class "Default")
      (node (ref "R36") (pin "1") (pinfunction "1_1") (pintype "passive"))
      (node (ref "R38") (pin "1") (pinfunction "1_1") (pintype "passive"))
      (node (ref "R41") (pin "2") (pinfunction "2_2") (pintype "passive"))
    )
    (net (code "55") (name "Net-(R43-Pad2)") (class "Default")
      (node (ref "R43") (pin "2") (pinfunction "2_2") (pintype "passive"))
      (node (ref "R48") (pin "2") (pinfunction "2_2") (pintype "passive"))
      (node (ref "U6") (pin "7") (pintype "passive"))
    )
    (net (code "56") (name "Net-(R44-Pad2)") (class "Default")
      (node (ref "R44") (pin "2") (pinfunction "2_2") (pintype "passive"))
      (node (ref "U6") (pin "3") (pintype "passive"))
    )
    (net (code "57") (name "Net-(R45-Pad1)") (class "Default")
      (node (ref "R45") (pin "1") (pinfunction "1_1") (pintype "passive"))
      (node (ref "R46") (pin "2") (pinfunction "2_2") (pintype "passive"))
      (node (ref "U6") (pin "2") (pintype "passive"))
    )
    (net (code "58") (name "Net-(R47-Pad2)") (class "Default")
      (node (ref "R47") (pin "2") (pinfunction "2_2") (pintype "passive"))
      (node (ref "U6") (pin "5") (pintype "passive"))
    )
    (net (code "59") (name "Net-(R48-Pad1)") (class "Default")
      (node (ref "R48") (pin "1") (pinfunction "1_1") (pintype "passive"))
      (node (ref "R49") (pin "1") (pinfunction "1_1") (pintype "passive"))
      (node (ref "U6") (pin "6") (pintype "passive"))
    )
    (net (code "60") (name "Net-(U1-FeedBack)") (class "Default")
      (node (ref "J2") (pin "2") (pinfunction "2_2") (pintype "passive"))
      (node (ref "R1") (pin "1") (pinfunction "1_1") (pintype "passive"))
      (node (ref "R3") (pin "2") (pinfunction "2_2") (pintype "passive"))
      (node (ref "U1") (pin "4") (pinfunction "FeedBack_4") (pintype "passive"))
    )
    (net (code "61") (name "Net-(U5-AREF)") (class "Default")
      (node (ref "C9") (pin "2") (pinfunction "2_2") (pintype "passive"))
      (node (ref "U5") (pin "20") (pinfunction "AREF_20") (pintype "passive"))
    )
    (net (code "62") (name "POWER") (class "Default")
      (node (ref "C1") (pin "1") (pinfunction "1_1") (pintype "passive"))
      (node (ref "LED1") (pin "1") (pinfunction "1_1") (pintype "passive"))
      (node (ref "LED1") (pin "5") (pinfunction "5_5") (pintype "passive"))
      (node (ref "Q1") (pin "2") (pinfunction "D_2") (pintype "input"))
      (node (ref "Q4") (pin "3") (pinfunction "E_3") (pintype "passive"))
      (node (ref "Q5") (pin "3") (pinfunction "E_3") (pintype "passive"))
      (node (ref "R13") (pin "2") (pinfunction "2_2") (pintype "passive"))
      (node (ref "R14") (pin "2") (pinfunction "2_2") (pintype "passive"))
      (node (ref "U1") (pin "1") (pinfunction "Vin_1") (pintype "passive"))
    )
    (net (code "63") (name "POWERIN") (class "Default")
      (node (ref "D1") (pin "2") (pinfunction "K_2") (pintype "passive"))
      (node (ref "D2") (pin "2") (pinfunction "K_2") (pintype "passive"))
      (node (ref "D3") (pin "2") (pinfunction "K_2") (pintype "passive"))
      (node (ref "Q1") (pin "3") (pinfunction "S_3") (pintype "input"))
      (node (ref "R2") (pin "2") (pinfunction "2_2") (pintype "passive"))
    )
    (net (code "64") (name "VCC") (class "Default")
      (node (ref "C10") (pin "2") (pinfunction "2_2") (pintype "passive"))
      (node (ref "C16") (pin "2") (pinfunction "2_2") (pintype "passive"))
      (node (ref "C3") (pin "1") (pinfunction "1_1") (pintype "passive"))
      (node (ref "C4") (pin "1") (pinfunction "1_1") (pintype "passive"))
      (node (ref "C5") (pin "1") (pinfunction "1_1") (pintype "passive"))
      (node (ref "C6") (pin "2") (pinfunction "2_2") (pintype "passive"))
      (node (ref "C7") (pin "2") (pinfunction "2_2") (pintype "passive"))
      (node (ref "D11") (pin "2") (pinfunction "K_2") (pintype "passive"))
      (node (ref "J6") (pin "2") (pinfunction "2_2") (pintype "passive"))
      (node (ref "J8") (pin "2") (pinfunction "2_2") (pintype "passive"))
      (node (ref "JP1") (pin "2") (pinfunction "2_2") (pintype "passive"))
      (node (ref "K1") (pin "7") (pinfunction "7_7") (pintype "passive"))
      (node (ref "L2") (pin "2") (pinfunction "2_2") (pintype "passive"))
      (node (ref "R10") (pin "2") (pinfunction "2_2") (pintype "passive"))
      (node (ref "R11") (pin "1") (pinfunction "1_1") (pintype "passive"))
      (node (ref "R12") (pin "1") (pinfunction "1_1") (pintype "passive"))
      (node (ref "R8") (pin "2") (pinfunction "2_2") (pintype "passive"))
      (node (ref "R9") (pin "2") (pinfunction "2_2") (pintype "passive"))
      (node (ref "U2") (pin "2") (pinfunction "VCC_2") (pintype "passive"))
      (node (ref "U5") (pin "18") (pinfunction "AVCC_18") (pintype "passive"))
      (node (ref "U5") (pin "4") (pinfunction "VCC_4") (pintype "passive"))
      (node (ref "U5") (pin "6") (pinfunction "VCC_6") (pintype "input"))
      (node (ref "U6") (pin "8") (pintype "passive"))
    )
    (net (code "65") (name "V_CHARGE") (class "Default")
      (node (ref "J1") (pin "2") (pinfunction "2_2") (pintype "passive"))
      (node (ref "K1") (pin "3") (pinfunction "3_3") (pintype "passive"))
      (node (ref "K1") (pin "6") (pinfunction "6_6") (pintype "passive"))
      (node (ref "R35") (pin "2") (pinfunction "2_2") (pintype "passive"))
    )
    (net (code "66") (name "unconnected-(J5-Pad2)") (class "Default")
      (node (ref "J5") (pin "2") (pinfunction "2_2") (pintype "passive"))
    )
    (net (code "67") (name "unconnected-(K1-Pad2)") (class "Default")
      (node (ref "K1") (pin "2") (pinfunction "2_2") (pintype "passive"))
    )
    (net (code "68") (name "unconnected-(K1-Pad5)") (class "Default")
      (node (ref "K1") (pin "5") (pinfunction "5_5") (pintype "passive"))
    )
    (net (code "69") (name "unconnected-(LED1-Pad3)") (class "Default")
      (node (ref "LED1") (pin "3") (pinfunction "3_3") (pintype "passive"))
    )
    (net (code "70") (name "unconnected-(U5-PB0_(ICP1)-Pad12)") (class "Default")
      (node (ref "U5") (pin "12") (pinfunction "PB0_(ICP1)_12") (pintype "passive"))
    )
  )
)
